# trans.net
KiCad netlist of a schematic drawn in EAGLE
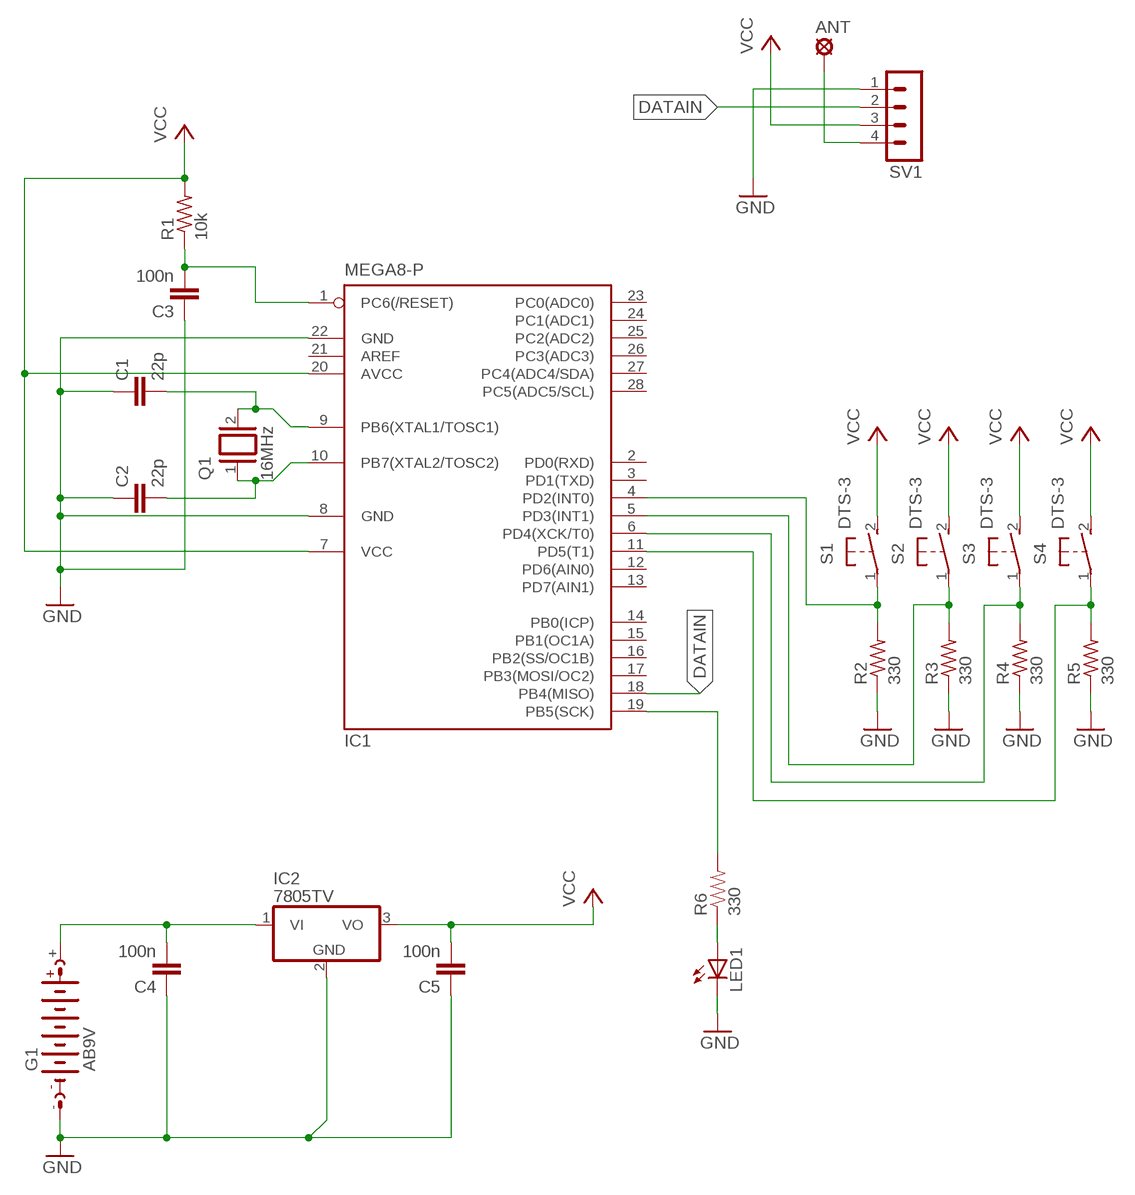
[diagram p0: schematic, sheet 1]

(export (version "E")
  (design (tool "Eeschema 10.0.6"))
  (components
    (comp (ref "ANT")
      (value "LSP10")
      (footprint "eagle-import:LSP10")
      (libsource (lib "eagle-import") (part "LSP10"))
    )
    (comp (ref "C1")
      (value "22p")
      (footprint "eagle-import:C025-024X044")
      (libsource (lib "eagle-import") (part "C-EU025-024X044"))
    )
    (comp (ref "C2")
      (value "22p")
      (footprint "eagle-import:C025-024X044")
      (libsource (lib "eagle-import") (part "C-EU025-024X044"))
    )
    (comp (ref "C3")
      (value "100n")
      (footprint "eagle-import:C025-024X044")
      (libsource (lib "eagle-import") (part "C-EU025-024X044"))
    )
    (comp (ref "C4")
      (value "100n")
      (footprint "eagle-import:C025-024X044")
      (libsource (lib "eagle-import") (part "C-EU025-024X044"))
    )
    (comp (ref "C5")
      (value "100n")
      (footprint "eagle-import:C025-024X044")
      (libsource (lib "eagle-import") (part "C-EU025-024X044"))
    )
    (comp (ref "G1")
      (value "AB9V")
      (footprint "eagle-import:AB9V")
      (libsource (lib "eagle-import") (part "AB9V"))
    )
    (comp (ref "IC1")
      (value "MEGA8-P")
      (footprint "eagle-import:DIL28-3")
      (libsource (lib "eagle-import") (part "MEGA8-P"))
    )
    (comp (ref "IC2")
      (value "7805TV")
      (footprint "eagle-import:TO220V")
      (libsource (lib "eagle-import") (part "78TV05"))
    )
    (comp (ref "LED1")
      (value "LED5MM")
      (footprint "eagle-import:LED5MM")
      (libsource (lib "eagle-import") (part "LED5MM"))
    )
    (comp (ref "Q1")
      (value "16MHz")
      (footprint "eagle-import:QS")
      (libsource (lib "eagle-import") (part "XTAL/S"))
    )
    (comp (ref "R1")
      (value "10k")
      (footprint "eagle-import:0204V")
      (libsource (lib "eagle-import") (part "R-US_0204/2V"))
    )
    (comp (ref "R2")
      (value "330")
      (footprint "eagle-import:0204V")
      (libsource (lib "eagle-import") (part "R-US_0204/2V"))
    )
    (comp (ref "R3")
      (value "330")
      (footprint "eagle-import:0204V")
      (libsource (lib "eagle-import") (part "R-US_0204/2V"))
    )
    (comp (ref "R4")
      (value "330")
      (footprint "eagle-import:0204V")
      (libsource (lib "eagle-import") (part "R-US_0204/2V"))
    )
    (comp (ref "R5")
      (value "330")
      (footprint "eagle-import:0204V")
      (libsource (lib "eagle-import") (part "R-US_0204/2V"))
    )
    (comp (ref "R6")
      (value "330")
      (footprint "eagle-import:AXIAL-0.4")
      (libsource (lib "eagle-import") (part "RESISTORPTH-1/4W"))
    )
    (comp (ref "S1")
      (value "DTS-3")
      (footprint "eagle-import:DTS-3")
      (libsource (lib "eagle-import") (part "DTS-3"))
    )
    (comp (ref "S2")
      (value "DTS-3")
      (footprint "eagle-import:DTS-3")
      (libsource (lib "eagle-import") (part "DTS-3"))
    )
    (comp (ref "S3")
      (value "DTS-3")
      (footprint "eagle-import:DTS-3")
      (libsource (lib "eagle-import") (part "DTS-3"))
    )
    (comp (ref "S4")
      (value "DTS-3")
      (footprint "eagle-import:DTS-3")
      (libsource (lib "eagle-import") (part "DTS-3"))
    )
    (comp (ref "SV1")
      (value "MA04-1")
      (footprint "eagle-import:MA04-1")
      (libsource (lib "eagle-import") (part "MA04-1"))
    )
  )
  (nets
    (net (code "1") (name "DATAIN") (class "Default")
      (node (ref "IC1") (pin "18") (pinfunction "PB4(MISO)_18") (pintype "bidirectional"))
      (node (ref "SV1") (pin "2") (pinfunction "2_2") (pintype "passive"))
    )
    (net (code "2") (name "GND") (class "Default")
      (node (ref "C1") (pin "1") (pinfunction "1_1") (pintype "passive"))
      (node (ref "C2") (pin "1") (pinfunction "1_1") (pintype "passive"))
      (node (ref "C3") (pin "1") (pinfunction "1_1") (pintype "passive"))
      (node (ref "C4") (pin "1") (pinfunction "1_1") (pintype "passive"))
      (node (ref "C5") (pin "1") (pinfunction "1_1") (pintype "passive"))
      (node (ref "G1") (pin "-") (pinfunction "-_-") (pintype "passive"))
      (node (ref "IC1") (pin "22") (pinfunction "GND_22") (pintype "power_in"))
      (node (ref "IC1") (pin "8") (pinfunction "GND_8") (pintype "power_in"))
      (node (ref "IC2") (pin "2") (pinfunction "GND_2") (pintype "passive"))
      (node (ref "LED1") (pin "K") (pinfunction "C_K") (pintype "passive"))
      (node (ref "R2") (pin "1") (pinfunction "1_1") (pintype "passive"))
      (node (ref "R3") (pin "1") (pinfunction "1_1") (pintype "passive"))
      (node (ref "R4") (pin "1") (pinfunction "1_1") (pintype "passive"))
      (node (ref "R5") (pin "1") (pinfunction "1_1") (pintype "passive"))
      (node (ref "SV1") (pin "1") (pinfunction "1_1") (pintype "passive"))
    )
    (net (code "3") (name "Net-(ANT-PadMP)") (class "Default")
      (node (ref "ANT") (pin "MP") (pinfunction "MP_MP") (pintype "passive"))
      (node (ref "SV1") (pin "4") (pinfunction "4_4") (pintype "passive"))
    )
    (net (code "4") (name "Net-(IC1-PB5(SCK))") (class "Default")
      (node (ref "IC1") (pin "19") (pinfunction "PB5(SCK)_19") (pintype "bidirectional"))
      (node (ref "R6") (pin "P$2") (pinfunction "2_P$2") (pintype "passive"))
    )
    (net (code "5") (name "Net-(IC1-PB6(XTAL1{slash}TOSC1))") (class "Default")
      (node (ref "C1") (pin "2") (pinfunction "2_2") (pintype "passive"))
      (node (ref "IC1") (pin "9") (pinfunction "PB6(XTAL1/TOSC1)_9") (pintype "bidirectional"))
      (node (ref "Q1") (pin "2") (pinfunction "2_2") (pintype "passive"))
    )
    (net (code "6") (name "Net-(IC1-PB7(XTAL2{slash}TOSC2))") (class "Default")
      (node (ref "C2") (pin "2") (pinfunction "2_2") (pintype "passive"))
      (node (ref "IC1") (pin "10") (pinfunction "PB7(XTAL2/TOSC2)_10") (pintype "bidirectional"))
      (node (ref "Q1") (pin "1") (pinfunction "1_1") (pintype "passive"))
    )
    (net (code "7") (name "Net-(IC1-PC6({slash}RESET))") (class "Default")
      (node (ref "C3") (pin "2") (pinfunction "2_2") (pintype "passive"))
      (node (ref "IC1") (pin "1") (pinfunction "PC6(/RESET)_1") (pintype "bidirectional"))
      (node (ref "R1") (pin "1") (pinfunction "1_1") (pintype "passive"))
    )
    (net (code "8") (name "Net-(IC1-PD2(INT0))") (class "Default")
      (node (ref "IC1") (pin "4") (pinfunction "PD2(INT0)_4") (pintype "bidirectional"))
      (node (ref "R2") (pin "2") (pinfunction "2_2") (pintype "passive"))
      (node (ref "S1") (pin "1") (pinfunction "1_1") (pintype "passive"))
    )
    (net (code "9") (name "Net-(IC1-PD3(INT1))") (class "Default")
      (node (ref "IC1") (pin "5") (pinfunction "PD3(INT1)_5") (pintype "bidirectional"))
      (node (ref "R3") (pin "2") (pinfunction "2_2") (pintype "passive"))
      (node (ref "S2") (pin "1") (pinfunction "1_1") (pintype "passive"))
    )
    (net (code "10") (name "Net-(IC1-PD4(XCK{slash}T0))") (class "Default")
      (node (ref "IC1") (pin "6") (pinfunction "PD4(XCK/T0)_6") (pintype "bidirectional"))
      (node (ref "R4") (pin "2") (pinfunction "2_2") (pintype "passive"))
      (node (ref "S3") (pin "1") (pinfunction "1_1") (pintype "passive"))
    )
    (net (code "11") (name "Net-(IC1-PD5(T1))") (class "Default")
      (node (ref "IC1") (pin "11") (pinfunction "PD5(T1)_11") (pintype "bidirectional"))
      (node (ref "R5") (pin "2") (pinfunction "2_2") (pintype "passive"))
      (node (ref "S4") (pin "1") (pinfunction "1_1") (pintype "passive"))
    )
    (net (code "12") (name "Net-(IC2-VI)") (class "Default")
      (node (ref "C4") (pin "2") (pinfunction "2_2") (pintype "passive"))
      (node (ref "G1") (pin "+") (pinfunction "+_+") (pintype "passive"))
      (node (ref "IC2") (pin "1") (pinfunction "VI_1") (pintype "input"))
    )
    (net (code "13") (name "Net-(R6-1)") (class "Default")
      (node (ref "LED1") (pin "A") (pinfunction "A_A") (pintype "passive"))
      (node (ref "R6") (pin "P$1") (pinfunction "1_P$1") (pintype "passive"))
    )
    (net (code "14") (name "VCC") (class "Default")
      (node (ref "C5") (pin "2") (pinfunction "2_2") (pintype "passive"))
      (node (ref "IC1") (pin "20") (pinfunction "AVCC_20") (pintype "power_in"))
      (node (ref "IC1") (pin "7") (pinfunction "VCC_7") (pintype "power_in"))
      (node (ref "IC2") (pin "3") (pinfunction "VO_3") (pintype "passive"))
      (node (ref "R1") (pin "2") (pinfunction "2_2") (pintype "passive"))
      (node (ref "S1") (pin "2") (pinfunction "2_2") (pintype "passive"))
      (node (ref "S2") (pin "2") (pinfunction "2_2") (pintype "passive"))
      (node (ref "S3") (pin "2") (pinfunction "2_2") (pintype "passive"))
      (node (ref "S4") (pin "2") (pinfunction "2_2") (pintype "passive"))
      (node (ref "SV1") (pin "3") (pinfunction "3_3") (pintype "passive"))
    )
    (net (code "15") (name "unconnected-(IC1-AREF-Pad21)") (class "Default")
      (node (ref "IC1") (pin "21") (pinfunction "AREF_21") (pintype "passive"))
    )
    (net (code "16") (name "unconnected-(IC1-PB0(ICP)-Pad14)") (class "Default")
      (node (ref "IC1") (pin "14") (pinfunction "PB0(ICP)_14") (pintype "bidirectional"))
    )
    (net (code "17") (name "unconnected-(IC1-PB1(OC1A)-Pad15)") (class "Default")
      (node (ref "IC1") (pin "15") (pinfunction "PB1(OC1A)_15") (pintype "bidirectional"))
    )
    (net (code "18") (name "unconnected-(IC1-PB2(SS{slash}OC1B)-Pad16)") (class "Default")
      (node (ref "IC1") (pin "16") (pinfunction "PB2(SS/OC1B)_16") (pintype "bidirectional"))
    )
    (net (code "19") (name "unconnected-(IC1-PB3(MOSI{slash}OC2)-Pad17)") (class "Default")
      (node (ref "IC1") (pin "17") (pinfunction "PB3(MOSI/OC2)_17") (pintype "bidirectional"))
    )
    (net (code "20") (name "unconnected-(IC1-PC0(ADC0)-Pad23)") (class "Default")
      (node (ref "IC1") (pin "23") (pinfunction "PC0(ADC0)_23") (pintype "bidirectional"))
    )
    (net (code "21") (name "unconnected-(IC1-PC1(ADC1)-Pad24)") (class "Default")
      (node (ref "IC1") (pin "24") (pinfunction "PC1(ADC1)_24") (pintype "bidirectional"))
    )
    (net (code "22") (name "unconnected-(IC1-PC2(ADC2)-Pad25)") (class "Default")
      (node (ref "IC1") (pin "25") (pinfunction "PC2(ADC2)_25") (pintype "bidirectional"))
    )
    (net (code "23") (name "unconnected-(IC1-PC3(ADC3)-Pad26)") (class "Default")
      (node (ref "IC1") (pin "26") (pinfunction "PC3(ADC3)_26") (pintype "bidirectional"))
    )
    (net (code "24") (name "unconnected-(IC1-PC4(ADC4{slash}SDA)-Pad27)") (class "Default")
      (node (ref "IC1") (pin "27") (pinfunction "PC4(ADC4/SDA)_27") (pintype "bidirectional"))
    )
    (net (code "25") (name "unconnected-(IC1-PC5(ADC5{slash}SCL)-Pad28)") (class "Default")
      (node (ref "IC1") (pin "28") (pinfunction "PC5(ADC5/SCL)_28") (pintype "bidirectional"))
    )
    (net (code "26") (name "unconnected-(IC1-PD0(RXD)-Pad2)") (class "Default")
      (node (ref "IC1") (pin "2") (pinfunction "PD0(RXD)_2") (pintype "bidirectional"))
    )
    (net (code "27") (name "unconnected-(IC1-PD1(TXD)-Pad3)") (class "Default")
      (node (ref "IC1") (pin "3") (pinfunction "PD1(TXD)_3") (pintype "bidirectional"))
    )
    (net (code "28") (name "unconnected-(IC1-PD6(AIN0)-Pad12)") (class "Default")
      (node (ref "IC1") (pin "12") (pinfunction "PD6(AIN0)_12") (pintype "bidirectional"))
    )
    (net (code "29") (name "unconnected-(IC1-PD7(AIN1)-Pad13)") (class "Default")
      (node (ref "IC1") (pin "13") (pinfunction "PD7(AIN1)_13") (pintype "bidirectional"))
    )
  )
)
